# AT24-Timer.net
KiCad netlist of a schematic drawn in EAGLE
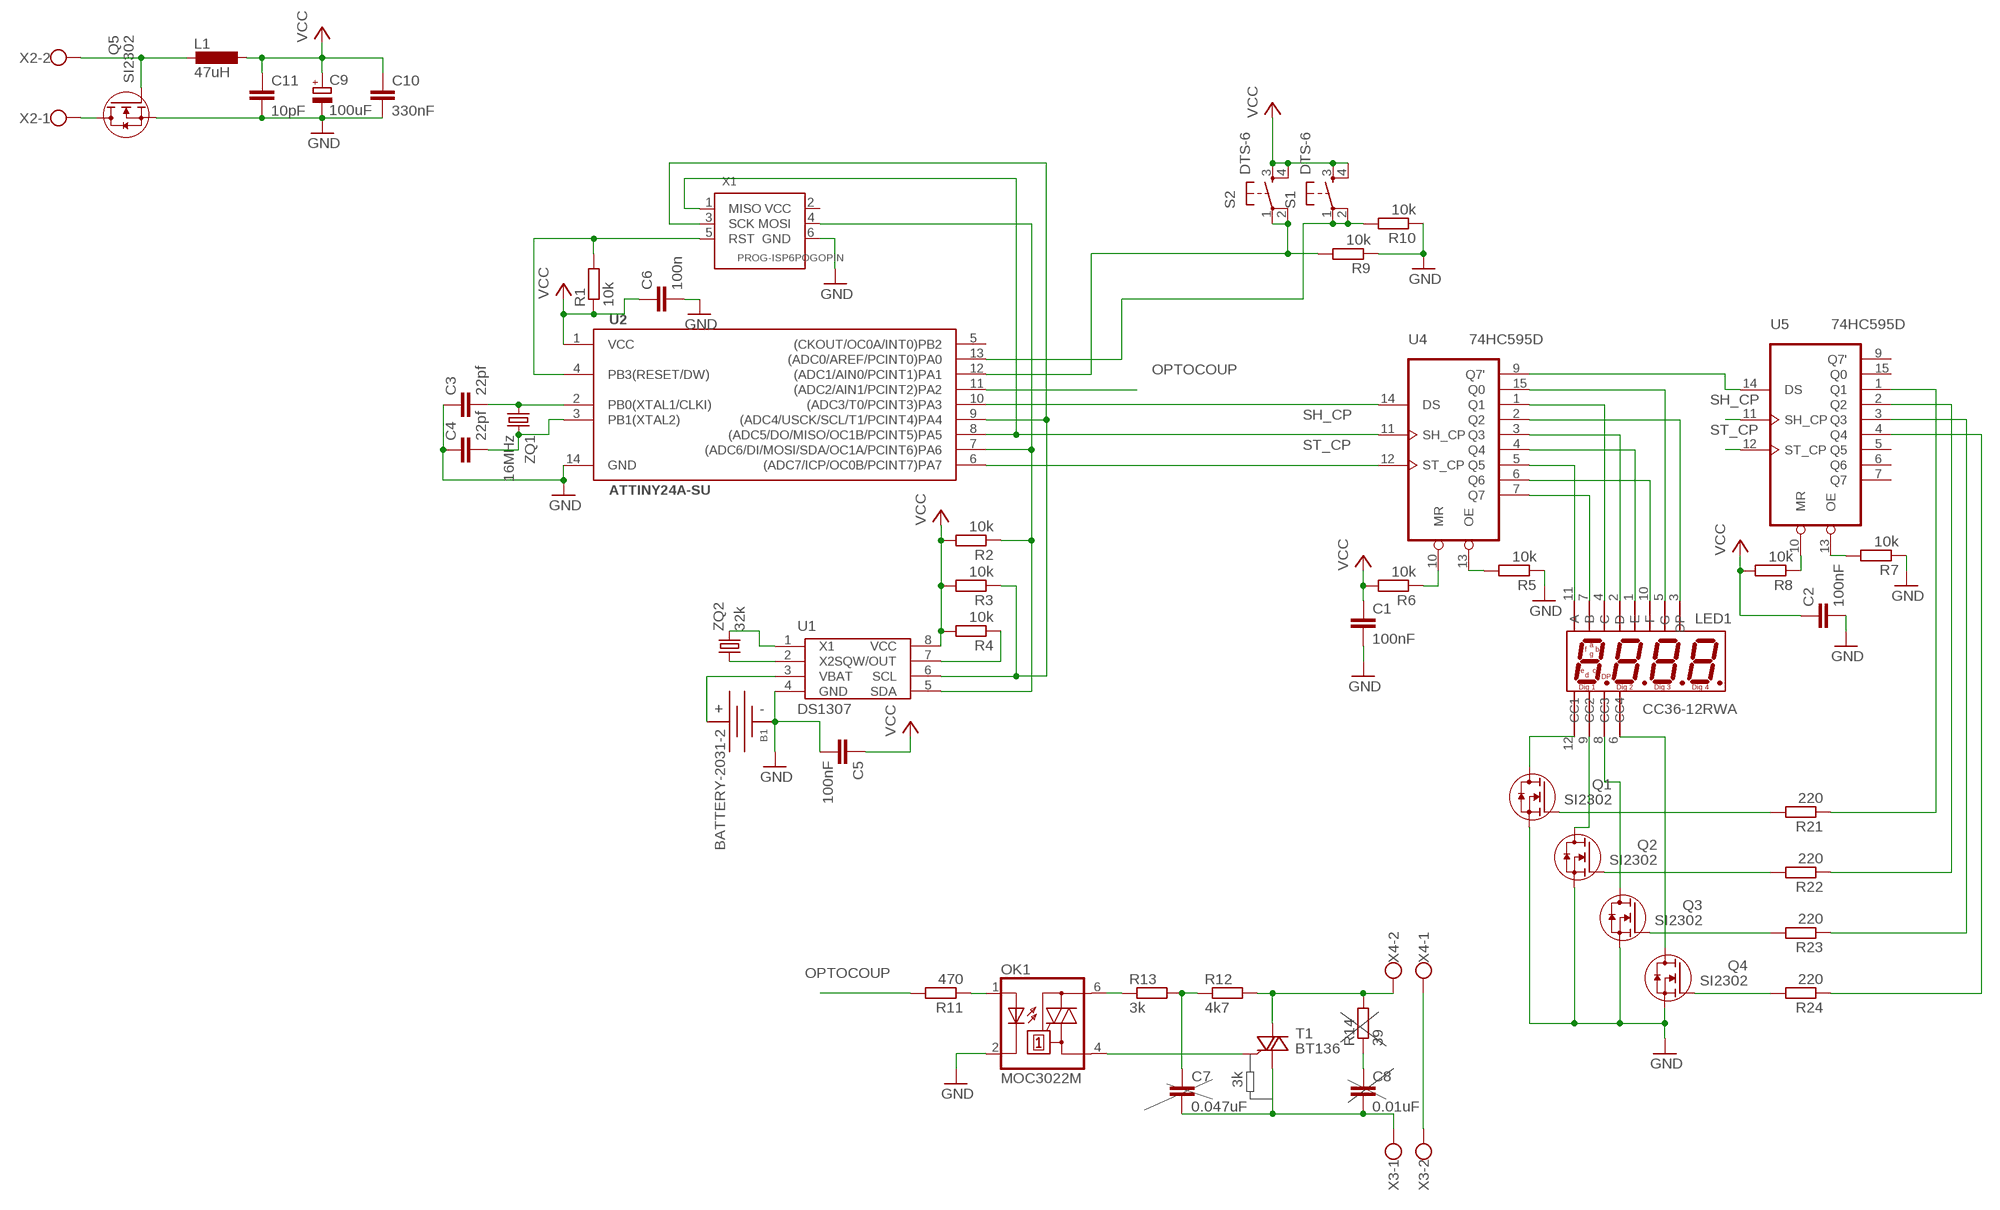
[diagram p0: schematic, sheet 1]

(export (version "E")
  (design (tool "Eeschema 10.0.6"))
  (components
    (comp (ref "B1")
      (value "BATTERY-2031-2")
      (footprint "eagle-import:BTH2032-2")
      (libsource (lib "eagle-import") (part "BATTERY-2031-2"))
    )
    (comp (ref "C1")
      (value "100nF")
      (footprint "eagle-import:C0603")
      (libsource (lib "eagle-import") (part "C-EUC0603"))
    )
    (comp (ref "C2")
      (value "100nF")
      (footprint "eagle-import:C0603")
      (libsource (lib "eagle-import") (part "C-EUC0603"))
    )
    (comp (ref "C3")
      (value "22pf")
      (footprint "eagle-import:C0603")
      (libsource (lib "eagle-import") (part "C-EUC0603"))
    )
    (comp (ref "C4")
      (value "22pf")
      (footprint "eagle-import:C0603")
      (libsource (lib "eagle-import") (part "C-EUC0603"))
    )
    (comp (ref "C5")
      (value "100nF")
      (footprint "eagle-import:C0603")
      (libsource (lib "eagle-import") (part "C-EUC0603"))
    )
    (comp (ref "C6")
      (value "100n")
      (footprint "eagle-import:C0603")
      (libsource (lib "eagle-import") (part "C-EUC0603"))
    )
    (comp (ref "C7")
      (value "0.047uF")
      (footprint "eagle-import:C150-054X183")
      (libsource (lib "eagle-import") (part "C-EU150-054X183"))
    )
    (comp (ref "C8")
      (value "0.01uF")
      (footprint "eagle-import:C102-043X133")
      (libsource (lib "eagle-import") (part "C-EU102-043X133"))
    )
    (comp (ref "C9")
      (value "100uF")
      (footprint "eagle-import:E2-5")
      (libsource (lib "eagle-import") (part "CPOL-EUE2-5"))
    )
    (comp (ref "C10")
      (value "330nF")
      (footprint "eagle-import:C0805")
      (libsource (lib "eagle-import") (part "C-EUC0805"))
    )
    (comp (ref "C11")
      (value "10pF")
      (footprint "eagle-import:C0805")
      (libsource (lib "eagle-import") (part "C-EUC0805"))
    )
    (comp (ref "L1")
      (value "47uH")
      (footprint "eagle-import:0204V")
      (libsource (lib "eagle-import") (part "L-EU0204V"))
    )
    (comp (ref "LED1")
      (value "CC36-12RWA")
      (footprint "eagle-import:7SEG_4DIG")
      (libsource (lib "eagle-import") (part "CC36-12RWA"))
    )
    (comp (ref "OK1")
      (value "MOC3022M")
      (footprint "eagle-import:DIL06")
      (fields (field (name "MF") "FAIRCHILD SEMICONDUCTOR") (field (name "MPN") "MOC3022-M"))
      (libsource (lib "eagle-import") (part "MOC30M22"))
    )
    (comp (ref "Q1")
      (value "SI2302")
      (footprint "eagle-import:SOT-23-GSD")
      (libsource (lib "eagle-import") (part "SI2302"))
    )
    (comp (ref "Q2")
      (value "SI2302")
      (footprint "eagle-import:SOT-23-GSD")
      (libsource (lib "eagle-import") (part "SI2302"))
    )
    (comp (ref "Q3")
      (value "SI2302")
      (footprint "eagle-import:SOT-23-GSD")
      (libsource (lib "eagle-import") (part "SI2302"))
    )
    (comp (ref "Q4")
      (value "SI2302")
      (footprint "eagle-import:SOT-23-GSD")
      (libsource (lib "eagle-import") (part "SI2302"))
    )
    (comp (ref "Q5")
      (value "SI2302")
      (footprint "eagle-import:SOT-23-GSD")
      (libsource (lib "eagle-import") (part "SI2302"))
    )
    (comp (ref "R1")
      (value "10k")
      (footprint "eagle-import:R0805")
      (libsource (lib "eagle-import") (part "R-EU_R0805"))
    )
    (comp (ref "R2")
      (value "10k")
      (footprint "eagle-import:R0805")
      (libsource (lib "eagle-import") (part "R-EU_R0805"))
    )
    (comp (ref "R3")
      (value "10k")
      (footprint "eagle-import:R0805")
      (libsource (lib "eagle-import") (part "R-EU_R0805"))
    )
    (comp (ref "R4")
      (value "10k")
      (footprint "eagle-import:R0805")
      (libsource (lib "eagle-import") (part "R-EU_R0805"))
    )
    (comp (ref "R5")
      (value "10k")
      (footprint "eagle-import:R0805")
      (libsource (lib "eagle-import") (part "R-EU_R0805"))
    )
    (comp (ref "R6")
      (value "10k")
      (footprint "eagle-import:R0805")
      (libsource (lib "eagle-import") (part "R-EU_R0805"))
    )
    (comp (ref "R7")
      (value "10k")
      (footprint "eagle-import:R0805")
      (libsource (lib "eagle-import") (part "R-EU_R0805"))
    )
    (comp (ref "R8")
      (value "10k")
      (footprint "eagle-import:R0805")
      (libsource (lib "eagle-import") (part "R-EU_R0805"))
    )
    (comp (ref "R9")
      (value "10k")
      (footprint "eagle-import:R0805")
      (libsource (lib "eagle-import") (part "R-EU_R0805"))
    )
    (comp (ref "R10")
      (value "10k")
      (footprint "eagle-import:R0805")
      (libsource (lib "eagle-import") (part "R-EU_R0805"))
    )
    (comp (ref "R11")
      (value "470")
      (footprint "eagle-import:R0805")
      (libsource (lib "eagle-import") (part "R-EU_R0805"))
    )
    (comp (ref "R12")
      (value "4k7")
      (footprint "eagle-import:0207_7")
      (libsource (lib "eagle-import") (part "R-EU_0207/7"))
    )
    (comp (ref "R13")
      (value "3k")
      (footprint "eagle-import:0207_7")
      (libsource (lib "eagle-import") (part "R-EU_0207/7"))
    )
    (comp (ref "R14")
      (value "39")
      (footprint "eagle-import:0207_7")
      (libsource (lib "eagle-import") (part "R-EU_0207/7"))
    )
    (comp (ref "R21")
      (value "220")
      (footprint "eagle-import:R0805")
      (libsource (lib "eagle-import") (part "R-EU_R0805"))
    )
    (comp (ref "R22")
      (value "220")
      (footprint "eagle-import:R0805")
      (libsource (lib "eagle-import") (part "R-EU_R0805"))
    )
    (comp (ref "R23")
      (value "220")
      (footprint "eagle-import:R0805")
      (libsource (lib "eagle-import") (part "R-EU_R0805"))
    )
    (comp (ref "R24")
      (value "220")
      (footprint "eagle-import:R0805")
      (libsource (lib "eagle-import") (part "R-EU_R0805"))
    )
    (comp (ref "S1")
      (value "DTS-6")
      (footprint "eagle-import:DTS-6")
      (libsource (lib "eagle-import") (part "DTS-6"))
    )
    (comp (ref "S2")
      (value "DTS-6")
      (footprint "eagle-import:DTS-6")
      (libsource (lib "eagle-import") (part "DTS-6"))
    )
    (comp (ref "T1")
      (value "BT136")
      (footprint "eagle-import:TO220AB")
      (libsource (lib "eagle-import") (part "BT136"))
    )
    (comp (ref "U1")
      (value "DS1307")
      (footprint "eagle-import:SOP08")
      (libsource (lib "eagle-import") (part "DS1307"))
    )
    (comp (ref "U2")
      (value "ATTINY24A-SU")
      (footprint "eagle-import:SO14")
      (libsource (lib "eagle-import") (part "ATTINY24A-SU"))
    )
    (comp (ref "U4")
      (value "74HC595D")
      (footprint "eagle-import:SO16")
      (libsource (lib "eagle-import") (part "74595DHC"))
    )
    (comp (ref "U5")
      (value "74HC595D")
      (footprint "eagle-import:SO16")
      (libsource (lib "eagle-import") (part "74595DHC"))
    )
    (comp (ref "X1")
      (value "PROG-ISP6POGOPIN")
      (footprint "eagle-import:PROG_POGOPIN")
      (libsource (lib "eagle-import") (part "PROG-ISP6POGOPIN"))
    )
    (comp (ref "X2")
      (value "W237-102")
      (footprint "eagle-import:W237-102")
      (fields (field (name "MPN") "237-102"))
      (libsource (lib "eagle-import") (part "W237-102"))
    )
    (comp (ref "X3")
      (value "W237-102")
      (footprint "eagle-import:W237-102")
      (fields (field (name "MPN") "237-102"))
      (libsource (lib "eagle-import") (part "W237-102"))
    )
    (comp (ref "X4")
      (value "W237-102")
      (footprint "eagle-import:W237-102")
      (fields (field (name "MPN") "237-102"))
      (libsource (lib "eagle-import") (part "W237-102"))
    )
    (comp (ref "ZQ1")
      (value "16MHz")
      (footprint "eagle-import:HC49_S")
      (libsource (lib "eagle-import") (part "CRYSTALHC49S"))
    )
    (comp (ref "ZQ2")
      (value "32k")
      (footprint "eagle-import:TC38H")
      (libsource (lib "eagle-import") (part "CRYSTALTC38H"))
    )
  )
  (nets
    (net (code "1") (name "/OPTOCOUP") (class "Default")
      (node (ref "R11") (pin "2") (pinfunction "2_2") (pintype "passive"))
      (node (ref "U2") (pin "11") (pinfunction "(ADC2/AIN1/PCINT2)PA2_11") (pintype "bidirectional"))
    )
    (net (code "2") (name "/SH_CP") (class "Default")
      (node (ref "U2") (pin "8") (pinfunction "(ADC5/DO/MISO/OC1B/PCINT5)PA5_8") (pintype "bidirectional"))
      (node (ref "U4") (pin "11") (pinfunction "SH_CP_11") (pintype "input"))
      (node (ref "U5") (pin "11") (pinfunction "SH_CP_11") (pintype "input"))
      (node (ref "X1") (pin "1") (pinfunction "MISO_1") (pintype "bidirectional"))
    )
    (net (code "3") (name "/ST_CP") (class "Default")
      (node (ref "U2") (pin "6") (pinfunction "(ADC7/ICP/OC0B/PCINT7)PA7_6") (pintype "bidirectional"))
      (node (ref "U4") (pin "12") (pinfunction "ST_CP_12") (pintype "input"))
      (node (ref "U5") (pin "12") (pinfunction "ST_CP_12") (pintype "input"))
    )
    (net (code "4") (name "GND") (class "Default")
      (node (ref "B1") (pin "-") (pinfunction "-_-") (pintype "power_in"))
      (node (ref "C1") (pin "2") (pinfunction "2_2") (pintype "passive"))
      (node (ref "C10") (pin "2") (pinfunction "2_2") (pintype "passive"))
      (node (ref "C11") (pin "2") (pinfunction "2_2") (pintype "passive"))
      (node (ref "C2") (pin "2") (pinfunction "2_2") (pintype "passive"))
      (node (ref "C3") (pin "1") (pinfunction "1_1") (pintype "passive"))
      (node (ref "C4") (pin "1") (pinfunction "1_1") (pintype "passive"))
      (node (ref "C5") (pin "2") (pinfunction "2_2") (pintype "passive"))
      (node (ref "C6") (pin "2") (pinfunction "2_2") (pintype "passive"))
      (node (ref "C9") (pin "-") (pinfunction "-_-") (pintype "passive"))
      (node (ref "OK1") (pin "2") (pinfunction "C_2") (pintype "passive"))
      (node (ref "Q1") (pin "S") (pinfunction "S_S") (pintype "passive"))
      (node (ref "Q2") (pin "S") (pinfunction "S_S") (pintype "passive"))
      (node (ref "Q3") (pin "S") (pinfunction "S_S") (pintype "passive"))
      (node (ref "Q4") (pin "S") (pinfunction "S_S") (pintype "passive"))
      (node (ref "Q5") (pin "S") (pinfunction "S_S") (pintype "passive"))
      (node (ref "R10") (pin "1") (pinfunction "1_1") (pintype "passive"))
      (node (ref "R5") (pin "1") (pinfunction "1_1") (pintype "passive"))
      (node (ref "R7") (pin "1") (pinfunction "1_1") (pintype "passive"))
      (node (ref "R9") (pin "1") (pinfunction "1_1") (pintype "passive"))
      (node (ref "U1") (pin "4") (pinfunction "GND_4") (pintype "power_in"))
      (node (ref "U2") (pin "14") (pinfunction "GND_14") (pintype "power_in"))
      (node (ref "X1") (pin "6") (pinfunction "GND_6") (pintype "power_in"))
    )
    (net (code "5") (name "Net-(C7-Pad1)") (class "Default")
      (node (ref "C7") (pin "1") (pinfunction "1_1") (pintype "passive"))
      (node (ref "R12") (pin "1") (pinfunction "1_1") (pintype "passive"))
      (node (ref "R13") (pin "2") (pinfunction "2_2") (pintype "passive"))
    )
    (net (code "6") (name "Net-(C8-Pad1)") (class "Default")
      (node (ref "C8") (pin "1") (pinfunction "1_1") (pintype "passive"))
      (node (ref "R14") (pin "1") (pinfunction "1_1") (pintype "passive"))
    )
    (net (code "7") (name "Net-(LED1-A)") (class "Default")
      (node (ref "LED1") (pin "11") (pinfunction "A_11") (pintype "input"))
      (node (ref "U4") (pin "5") (pinfunction "Q5_5") (pintype "output"))
    )
    (net (code "8") (name "Net-(LED1-B)") (class "Default")
      (node (ref "LED1") (pin "7") (pinfunction "B_7") (pintype "input"))
      (node (ref "U4") (pin "7") (pinfunction "Q7_7") (pintype "output"))
    )
    (net (code "9") (name "Net-(LED1-C)") (class "Default")
      (node (ref "LED1") (pin "4") (pinfunction "C_4") (pintype "input"))
      (node (ref "U4") (pin "1") (pinfunction "Q1_1") (pintype "output"))
    )
    (net (code "10") (name "Net-(LED1-CC1)") (class "Default")
      (node (ref "LED1") (pin "12") (pinfunction "CC1_12") (pintype "input"))
      (node (ref "Q1") (pin "D") (pinfunction "D_D") (pintype "passive"))
    )
    (net (code "11") (name "Net-(LED1-CC2)") (class "Default")
      (node (ref "LED1") (pin "9") (pinfunction "CC2_9") (pintype "input"))
      (node (ref "Q2") (pin "D") (pinfunction "D_D") (pintype "passive"))
    )
    (net (code "12") (name "Net-(LED1-CC3)") (class "Default")
      (node (ref "LED1") (pin "8") (pinfunction "CC3_8") (pintype "input"))
      (node (ref "Q3") (pin "D") (pinfunction "D_D") (pintype "passive"))
    )
    (net (code "13") (name "Net-(LED1-CC4)") (class "Default")
      (node (ref "LED1") (pin "6") (pinfunction "CC4_6") (pintype "input"))
      (node (ref "Q4") (pin "D") (pinfunction "D_D") (pintype "passive"))
    )
    (net (code "14") (name "Net-(LED1-D)") (class "Default")
      (node (ref "LED1") (pin "2") (pinfunction "D_2") (pintype "input"))
      (node (ref "U4") (pin "3") (pinfunction "Q3_3") (pintype "output"))
    )
    (net (code "15") (name "Net-(LED1-DP)") (class "Default")
      (node (ref "LED1") (pin "3") (pinfunction "DP_3") (pintype "input"))
      (node (ref "U4") (pin "2") (pinfunction "Q2_2") (pintype "output"))
    )
    (net (code "16") (name "Net-(LED1-E)") (class "Default")
      (node (ref "LED1") (pin "1") (pinfunction "E_1") (pintype "input"))
      (node (ref "U4") (pin "4") (pinfunction "Q4_4") (pintype "output"))
    )
    (net (code "17") (name "Net-(LED1-F)") (class "Default")
      (node (ref "LED1") (pin "10") (pinfunction "F_10") (pintype "input"))
      (node (ref "U4") (pin "6") (pinfunction "Q6_6") (pintype "output"))
    )
    (net (code "18") (name "Net-(LED1-G)") (class "Default")
      (node (ref "LED1") (pin "5") (pinfunction "G_5") (pintype "input"))
      (node (ref "U4") (pin "15") (pinfunction "Q0_15") (pintype "output"))
    )
    (net (code "19") (name "Net-(OK1-A)") (class "Default")
      (node (ref "OK1") (pin "1") (pinfunction "A_1") (pintype "passive"))
      (node (ref "R11") (pin "1") (pinfunction "1_1") (pintype "passive"))
    )
    (net (code "20") (name "Net-(OK1-A1)") (class "Default")
      (node (ref "OK1") (pin "4") (pinfunction "A1_4") (pintype "passive"))
      (node (ref "T1") (pin "3") (pinfunction "G_3") (pintype "passive"))
    )
    (net (code "21") (name "Net-(OK1-A2)") (class "Default")
      (node (ref "OK1") (pin "6") (pinfunction "A2_6") (pintype "passive"))
      (node (ref "R13") (pin "1") (pinfunction "1_1") (pintype "passive"))
    )
    (net (code "22") (name "Net-(Q1-PadG)") (class "Default")
      (node (ref "Q1") (pin "G") (pinfunction "G_G") (pintype "passive"))
      (node (ref "R21") (pin "2") (pinfunction "2_2") (pintype "passive"))
    )
    (net (code "23") (name "Net-(Q2-PadG)") (class "Default")
      (node (ref "Q2") (pin "G") (pinfunction "G_G") (pintype "passive"))
      (node (ref "R22") (pin "2") (pinfunction "2_2") (pintype "passive"))
    )
    (net (code "24") (name "Net-(Q3-PadG)") (class "Default")
      (node (ref "Q3") (pin "G") (pinfunction "G_G") (pintype "passive"))
      (node (ref "R23") (pin "2") (pinfunction "2_2") (pintype "passive"))
    )
    (net (code "25") (name "Net-(Q4-PadG)") (class "Default")
      (node (ref "Q4") (pin "G") (pinfunction "G_G") (pintype "passive"))
      (node (ref "R24") (pin "2") (pinfunction "2_2") (pintype "passive"))
    )
    (net (code "26") (name "Net-(T1-A1)") (class "Default")
      (node (ref "C7") (pin "2") (pinfunction "2_2") (pintype "passive"))
      (node (ref "C8") (pin "2") (pinfunction "2_2") (pintype "passive"))
      (node (ref "T1") (pin "1") (pinfunction "A1_1") (pintype "passive"))
      (node (ref "X3") (pin "1") (pinfunction "KL_1") (pintype "passive"))
    )
    (net (code "27") (name "Net-(T1-A2)") (class "Default")
      (node (ref "R12") (pin "2") (pinfunction "2_2") (pintype "passive"))
      (node (ref "R14") (pin "2") (pinfunction "2_2") (pintype "passive"))
      (node (ref "T1") (pin "2") (pinfunction "A2_2") (pintype "passive"))
      (node (ref "X4") (pin "2") (pinfunction "KL_2") (pintype "passive"))
    )
    (net (code "28") (name "Net-(U1-SCL)") (class "Default")
      (node (ref "R3") (pin "1") (pinfunction "1_1") (pintype "passive"))
      (node (ref "U1") (pin "6") (pinfunction "SCL_6") (pintype "bidirectional"))
      (node (ref "U2") (pin "9") (pinfunction "(ADC4/USCK/SCL/T1/PCINT4)PA4_9") (pintype "bidirectional"))
      (node (ref "X1") (pin "3") (pinfunction "SCK_3") (pintype "bidirectional"))
    )
    (net (code "29") (name "Net-(U1-SDA)") (class "Default")
      (node (ref "R2") (pin "1") (pinfunction "1_1") (pintype "passive"))
      (node (ref "U1") (pin "5") (pinfunction "SDA_5") (pintype "bidirectional"))
      (node (ref "U2") (pin "7") (pinfunction "(ADC6/DI/MOSI/SDA/OC1A/PCINT6)PA6_7") (pintype "bidirectional"))
      (node (ref "X1") (pin "4") (pinfunction "MOSI_4") (pintype "bidirectional"))
    )
    (net (code "30") (name "Net-(U1-SQW{slash}OUT)") (class "Default")
      (node (ref "R4") (pin "1") (pinfunction "1_1") (pintype "passive"))
      (node (ref "U1") (pin "7") (pinfunction "SQW/OUT_7") (pintype "bidirectional"))
    )
    (net (code "31") (name "Net-(U1-VBAT)") (class "Default")
      (node (ref "B1") (pin "+") (pinfunction "+_+") (pintype "power_in"))
      (node (ref "U1") (pin "3") (pinfunction "VBAT_3") (pintype "power_in"))
    )
    (net (code "32") (name "Net-(U1-X1)") (class "Default")
      (node (ref "U1") (pin "1") (pinfunction "X1_1") (pintype "passive"))
      (node (ref "ZQ2") (pin "2") (pinfunction "2_2") (pintype "passive"))
    )
    (net (code "33") (name "Net-(U1-X2)") (class "Default")
      (node (ref "U1") (pin "2") (pinfunction "X2_2") (pintype "passive"))
      (node (ref "ZQ2") (pin "1") (pinfunction "1_1") (pintype "passive"))
    )
    (net (code "34") (name "Net-(U2-(ADC0{slash}AREF{slash}PCINT0)PA0)") (class "Default")
      (node (ref "R10") (pin "2") (pinfunction "2_2") (pintype "passive"))
      (node (ref "S1") (pin "1") (pinfunction "1_1") (pintype "passive"))
      (node (ref "S1") (pin "2") (pinfunction "2_2") (pintype "passive"))
      (node (ref "U2") (pin "13") (pinfunction "(ADC0/AREF/PCINT0)PA0_13") (pintype "bidirectional"))
    )
    (net (code "35") (name "Net-(U2-(ADC1{slash}AIN0{slash}PCINT1)PA1)") (class "Default")
      (node (ref "R9") (pin "2") (pinfunction "2_2") (pintype "passive"))
      (node (ref "S2") (pin "1") (pinfunction "1_1") (pintype "passive"))
      (node (ref "S2") (pin "2") (pinfunction "2_2") (pintype "passive"))
      (node (ref "U2") (pin "12") (pinfunction "(ADC1/AIN0/PCINT1)PA1_12") (pintype "bidirectional"))
    )
    (net (code "36") (name "Net-(U2-(ADC3{slash}T0{slash}PCINT3)PA3)") (class "Default")
      (node (ref "U2") (pin "10") (pinfunction "(ADC3/T0/PCINT3)PA3_10") (pintype "bidirectional"))
      (node (ref "U4") (pin "14") (pinfunction "DS_14") (pintype "input"))
    )
    (net (code "37") (name "Net-(U2-PB0(XTAL1{slash}CLKI))") (class "Default")
      (node (ref "C3") (pin "2") (pinfunction "2_2") (pintype "passive"))
      (node (ref "U2") (pin "2") (pinfunction "PB0(XTAL1/CLKI)_2") (pintype "bidirectional"))
      (node (ref "ZQ1") (pin "1") (pinfunction "1_1") (pintype "passive"))
    )
    (net (code "38") (name "Net-(U2-PB1(XTAL2))") (class "Default")
      (node (ref "C4") (pin "2") (pinfunction "2_2") (pintype "passive"))
      (node (ref "U2") (pin "3") (pinfunction "PB1(XTAL2)_3") (pintype "bidirectional"))
      (node (ref "ZQ1") (pin "2") (pinfunction "2_2") (pintype "passive"))
    )
    (net (code "39") (name "Net-(U2-PB3(RESET{slash}DW))") (class "Default")
      (node (ref "R1") (pin "2") (pinfunction "2_2") (pintype "passive"))
      (node (ref "U2") (pin "4") (pinfunction "PB3(RESET/DW)_4") (pintype "bidirectional"))
      (node (ref "X1") (pin "5") (pinfunction "RST_5") (pintype "bidirectional"))
    )
    (net (code "40") (name "Net-(U4A-MR)") (class "Default")
      (node (ref "R6") (pin "1") (pinfunction "1_1") (pintype "passive"))
      (node (ref "U4") (pin "10") (pinfunction "MR_10") (pintype "input"))
    )
    (net (code "41") (name "Net-(U4A-OE)") (class "Default")
      (node (ref "R5") (pin "2") (pinfunction "2_2") (pintype "passive"))
      (node (ref "U4") (pin "13") (pinfunction "OE_13") (pintype "input"))
    )
    (net (code "42") (name "Net-(U4A-Q7')") (class "Default")
      (node (ref "U4") (pin "9") (pinfunction "Q7'_9") (pintype "output"))
      (node (ref "U5") (pin "14") (pinfunction "DS_14") (pintype "input"))
    )
    (net (code "43") (name "Net-(U5A-MR)") (class "Default")
      (node (ref "R8") (pin "1") (pinfunction "1_1") (pintype "passive"))
      (node (ref "U5") (pin "10") (pinfunction "MR_10") (pintype "input"))
    )
    (net (code "44") (name "Net-(U5A-OE)") (class "Default")
      (node (ref "R7") (pin "2") (pinfunction "2_2") (pintype "passive"))
      (node (ref "U5") (pin "13") (pinfunction "OE_13") (pintype "input"))
    )
    (net (code "45") (name "Net-(U5A-Q1)") (class "Default")
      (node (ref "R21") (pin "1") (pinfunction "1_1") (pintype "passive"))
      (node (ref "U5") (pin "1") (pinfunction "Q1_1") (pintype "output"))
    )
    (net (code "46") (name "Net-(U5A-Q2)") (class "Default")
      (node (ref "R22") (pin "1") (pinfunction "1_1") (pintype "passive"))
      (node (ref "U5") (pin "2") (pinfunction "Q2_2") (pintype "output"))
    )
    (net (code "47") (name "Net-(U5A-Q3)") (class "Default")
      (node (ref "R23") (pin "1") (pinfunction "1_1") (pintype "passive"))
      (node (ref "U5") (pin "3") (pinfunction "Q3_3") (pintype "output"))
    )
    (net (code "48") (name "Net-(U5A-Q4)") (class "Default")
      (node (ref "R24") (pin "1") (pinfunction "1_1") (pintype "passive"))
      (node (ref "U5") (pin "4") (pinfunction "Q4_4") (pintype "output"))
    )
    (net (code "49") (name "Net-(X2A-KL)") (class "Default")
      (node (ref "Q5") (pin "D") (pinfunction "D_D") (pintype "passive"))
      (node (ref "X2") (pin "1") (pinfunction "KL_1") (pintype "passive"))
    )
    (net (code "50") (name "Net-(X2B-KL)") (class "Default")
      (node (ref "L1") (pin "2") (pinfunction "2_2") (pintype "passive"))
      (node (ref "Q5") (pin "G") (pinfunction "G_G") (pintype "passive"))
      (node (ref "X2") (pin "2") (pinfunction "KL_2") (pintype "passive"))
    )
    (net (code "51") (name "Net-(X3B-KL)") (class "Default")
      (node (ref "X3") (pin "2") (pinfunction "KL_2") (pintype "passive"))
      (node (ref "X4") (pin "1") (pinfunction "KL_1") (pintype "passive"))
    )
    (net (code "52") (name "VCC") (class "Default")
      (node (ref "C1") (pin "1") (pinfunction "1_1") (pintype "passive"))
      (node (ref "C10") (pin "1") (pinfunction "1_1") (pintype "passive"))
      (node (ref "C11") (pin "1") (pinfunction "1_1") (pintype "passive"))
      (node (ref "C2") (pin "1") (pinfunction "1_1") (pintype "passive"))
      (node (ref "C5") (pin "1") (pinfunction "1_1") (pintype "passive"))
      (node (ref "C6") (pin "1") (pinfunction "1_1") (pintype "passive"))
      (node (ref "C9") (pin "+") (pinfunction "+_+") (pintype "passive"))
      (node (ref "L1") (pin "1") (pinfunction "1_1") (pintype "passive"))
      (node (ref "R1") (pin "1") (pinfunction "1_1") (pintype "passive"))
      (node (ref "R2") (pin "2") (pinfunction "2_2") (pintype "passive"))
      (node (ref "R3") (pin "2") (pinfunction "2_2") (pintype "passive"))
      (node (ref "R4") (pin "2") (pinfunction "2_2") (pintype "passive"))
      (node (ref "R6") (pin "2") (pinfunction "2_2") (pintype "passive"))
      (node (ref "R8") (pin "2") (pinfunction "2_2") (pintype "passive"))
      (node (ref "S1") (pin "3") (pinfunction "3_3") (pintype "passive"))
      (node (ref "S1") (pin "4") (pinfunction "4_4") (pintype "passive"))
      (node (ref "S2") (pin "3") (pinfunction "3_3") (pintype "passive"))
      (node (ref "S2") (pin "4") (pinfunction "4_4") (pintype "passive"))
      (node (ref "U1") (pin "8") (pinfunction "VCC_8") (pintype "power_in"))
      (node (ref "U2") (pin "1") (pinfunction "VCC_1") (pintype "power_in"))
    )
    (net (code "53") (name "unconnected-(U2-(CKOUT{slash}OC0A{slash}INT0)PB2-Pad5)") (class "Default")
      (node (ref "U2") (pin "5") (pinfunction "(CKOUT/OC0A/INT0)PB2_5") (pintype "bidirectional"))
    )
    (net (code "54") (name "unconnected-(U5A-Q0-Pad15)") (class "Default")
      (node (ref "U5") (pin "15") (pinfunction "Q0_15") (pintype "output"))
    )
    (net (code "55") (name "unconnected-(U5A-Q5-Pad5)") (class "Default")
      (node (ref "U5") (pin "5") (pinfunction "Q5_5") (pintype "output"))
    )
    (net (code "56") (name "unconnected-(U5A-Q6-Pad6)") (class "Default")
      (node (ref "U5") (pin "6") (pinfunction "Q6_6") (pintype "output"))
    )
    (net (code "57") (name "unconnected-(U5A-Q7'-Pad9)") (class "Default")
      (node (ref "U5") (pin "9") (pinfunction "Q7'_9") (pintype "output"))
    )
    (net (code "58") (name "unconnected-(U5A-Q7-Pad7)") (class "Default")
      (node (ref "U5") (pin "7") (pinfunction "Q7_7") (pintype "output"))
    )
    (net (code "59") (name "unconnected-(X1-VCC-Pad2)") (class "Default")
      (node (ref "X1") (pin "2") (pinfunction "VCC_2") (pintype "bidirectional"))
    )
  )
)
